# Status_Board.net
KiCad netlist of a schematic drawn in EAGLE
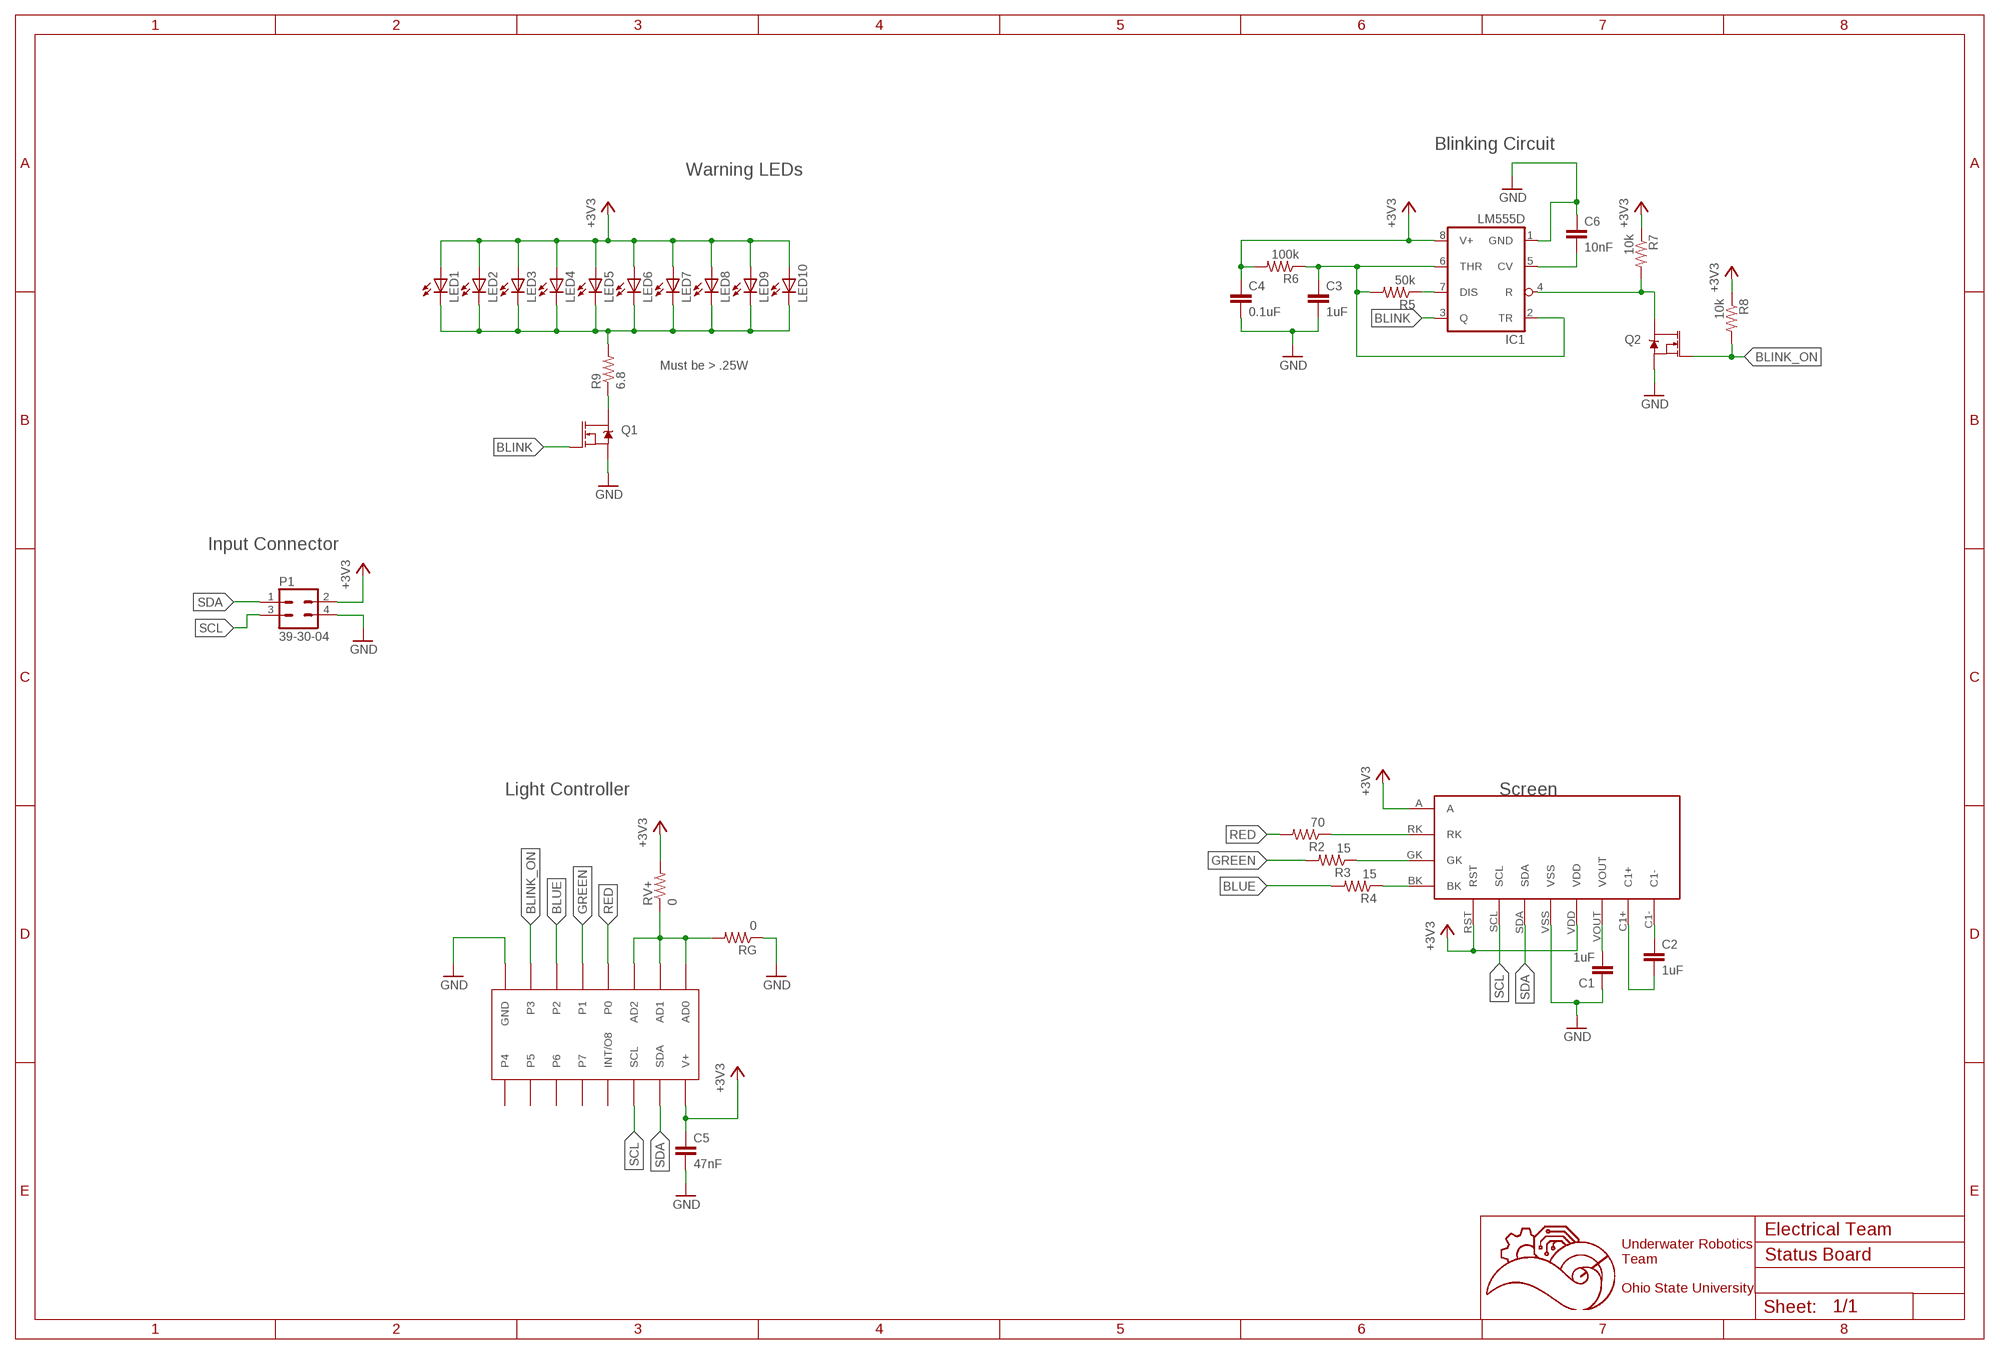
[diagram p0: schematic, sheet 1]

(export (version "E")
  (design (tool "Eeschema 10.0.6"))
  (components
    (comp (ref "C1")
      (value "1uF")
      (footprint "eagle-import:C0603")
      (libsource (lib "eagle-import") (part "C-EUC0603"))
    )
    (comp (ref "C2")
      (value "1uF")
      (footprint "eagle-import:C0603")
      (libsource (lib "eagle-import") (part "C-EUC0603"))
    )
    (comp (ref "C3")
      (value "1uF")
      (footprint "eagle-import:C0603")
      (libsource (lib "eagle-import") (part "C-EUC0603"))
    )
    (comp (ref "C4")
      (value "0.1uF")
      (footprint "eagle-import:C0603")
      (libsource (lib "eagle-import") (part "C-EUC0603"))
    )
    (comp (ref "C5")
      (value "47nF")
      (footprint "eagle-import:C0603")
      (libsource (lib "eagle-import") (part "C-EUC0603"))
    )
    (comp (ref "C6")
      (value "10nF")
      (footprint "eagle-import:C0603")
      (libsource (lib "eagle-import") (part "C-EUC0603"))
    )
    (comp (ref "IC1")
      (value "LM555D")
      (footprint "eagle-import:SO08")
      (libsource (lib "eagle-import") (part "555DLM"))
    )
    (comp (ref "LED1")
      (value "LEDCHIPLED_0603")
      (footprint "eagle-import:CHIPLED_0603")
      (libsource (lib "eagle-import") (part "LEDCHIPLED_0603"))
    )
    (comp (ref "LED2")
      (value "LEDCHIPLED_0603")
      (footprint "eagle-import:CHIPLED_0603")
      (libsource (lib "eagle-import") (part "LEDCHIPLED_0603"))
    )
    (comp (ref "LED3")
      (value "LEDCHIPLED_0603")
      (footprint "eagle-import:CHIPLED_0603")
      (libsource (lib "eagle-import") (part "LEDCHIPLED_0603"))
    )
    (comp (ref "LED4")
      (value "LEDCHIPLED_0603")
      (footprint "eagle-import:CHIPLED_0603")
      (libsource (lib "eagle-import") (part "LEDCHIPLED_0603"))
    )
    (comp (ref "LED5")
      (value "LEDCHIPLED_0603")
      (footprint "eagle-import:CHIPLED_0603")
      (libsource (lib "eagle-import") (part "LEDCHIPLED_0603"))
    )
    (comp (ref "LED6")
      (value "LEDCHIPLED_0603")
      (footprint "eagle-import:CHIPLED_0603")
      (libsource (lib "eagle-import") (part "LEDCHIPLED_0603"))
    )
    (comp (ref "LED7")
      (value "LEDCHIPLED_0603")
      (footprint "eagle-import:CHIPLED_0603")
      (libsource (lib "eagle-import") (part "LEDCHIPLED_0603"))
    )
    (comp (ref "LED8")
      (value "LEDCHIPLED_0603")
      (footprint "eagle-import:CHIPLED_0603")
      (libsource (lib "eagle-import") (part "LEDCHIPLED_0603"))
    )
    (comp (ref "LED9")
      (value "LEDCHIPLED_0603")
      (footprint "eagle-import:CHIPLED_0603")
      (libsource (lib "eagle-import") (part "LEDCHIPLED_0603"))
    )
    (comp (ref "LED10")
      (value "LEDCHIPLED_0603")
      (footprint "eagle-import:CHIPLED_0603")
      (libsource (lib "eagle-import") (part "LEDCHIPLED_0603"))
    )
    (comp (ref "P1")
      (value "39-30-04")
      (footprint "eagle-import:39-30-_04_")
      (libsource (lib "eagle-import") (part "39-30-?04?"))
    )
    (comp (ref "Q1")
      (value "310mA/60V/1.6Ω")
      (footprint "eagle-import:SOT323")
      (libsource (lib "eagle-import") (part "MOSFET-NCH-2N7002PW"))
    )
    (comp (ref "Q2")
      (value "310mA/60V/1.6Ω")
      (footprint "eagle-import:SOT323")
      (libsource (lib "eagle-import") (part "MOSFET-NCH-2N7002PW"))
    )
    (comp (ref "R2")
      (value "70")
      (footprint "eagle-import:R0603")
      (libsource (lib "eagle-import") (part "R-US_R0603"))
    )
    (comp (ref "R3")
      (value "15")
      (footprint "eagle-import:R0603")
      (libsource (lib "eagle-import") (part "R-US_R0603"))
    )
    (comp (ref "R4")
      (value "15")
      (footprint "eagle-import:R0603")
      (libsource (lib "eagle-import") (part "R-US_R0603"))
    )
    (comp (ref "R5")
      (value "50k")
      (footprint "eagle-import:R0603")
      (libsource (lib "eagle-import") (part "R-US_R0603"))
    )
    (comp (ref "R6")
      (value "100k")
      (footprint "eagle-import:R0603")
      (libsource (lib "eagle-import") (part "R-US_R0603"))
    )
    (comp (ref "R7")
      (value "10k")
      (footprint "eagle-import:R0603")
      (libsource (lib "eagle-import") (part "R-US_R0603"))
    )
    (comp (ref "R8")
      (value "10k")
      (footprint "eagle-import:R0603")
      (libsource (lib "eagle-import") (part "R-US_R0603"))
    )
    (comp (ref "R9")
      (value "6.8")
      (footprint "eagle-import:R0603")
      (libsource (lib "eagle-import") (part "R-US_R0603"))
    )
    (comp (ref "RG")
      (value "0")
      (footprint "eagle-import:R0603")
      (libsource (lib "eagle-import") (part "R-US_R0603"))
    )
    (comp (ref "RV+")
      (value "0")
      (footprint "eagle-import:R0603")
      (libsource (lib "eagle-import") (part "R-US_R0603"))
    )
    (comp (ref "U$1")
      (value "NHD-C0220BIZ")
      (footprint "eagle-import:NHD-C0220BIZ")
      (libsource (lib "eagle-import") (part "NHD-C0220BIZ"))
    )
    (comp (ref "U$2")
      (value "MAX7315")
      (footprint "eagle-import:TSSOP-16")
      (libsource (lib "eagle-import") (part "MAX7315"))
    )
  )
  (nets
    (net (code "1") (name "+3V3") (class "Default")
      (node (ref "C4") (pin "1") (pinfunction "1_1") (pintype "passive"))
      (node (ref "C5") (pin "1") (pinfunction "1_1") (pintype "passive"))
      (node (ref "IC1") (pin "8") (pinfunction "V+_8") (pintype "power_in"))
      (node (ref "LED1") (pin "A") (pinfunction "A_A") (pintype "passive"))
      (node (ref "LED10") (pin "A") (pinfunction "A_A") (pintype "passive"))
      (node (ref "LED2") (pin "A") (pinfunction "A_A") (pintype "passive"))
      (node (ref "LED3") (pin "A") (pinfunction "A_A") (pintype "passive"))
      (node (ref "LED4") (pin "A") (pinfunction "A_A") (pintype "passive"))
      (node (ref "LED5") (pin "A") (pinfunction "A_A") (pintype "passive"))
      (node (ref "LED6") (pin "A") (pinfunction "A_A") (pintype "passive"))
      (node (ref "LED7") (pin "A") (pinfunction "A_A") (pintype "passive"))
      (node (ref "LED8") (pin "A") (pinfunction "A_A") (pintype "passive"))
      (node (ref "LED9") (pin "A") (pinfunction "A_A") (pintype "passive"))
      (node (ref "P1") (pin "2") (pinfunction "2_2") (pintype "passive"))
      (node (ref "R6") (pin "2") (pinfunction "2_2") (pintype "passive"))
      (node (ref "R7") (pin "1") (pinfunction "1_1") (pintype "passive"))
      (node (ref "R8") (pin "1") (pinfunction "1_1") (pintype "passive"))
      (node (ref "RV+") (pin "2") (pinfunction "2_2") (pintype "passive"))
      (node (ref "U$1") (pin "A") (pinfunction "A_A") (pintype "bidirectional"))
      (node (ref "U$1") (pin "RST") (pinfunction "RST_RST") (pintype "bidirectional"))
      (node (ref "U$1") (pin "VDD") (pinfunction "VDD_VDD") (pintype "bidirectional"))
      (node (ref "U$2") (pin "16") (pinfunction "V+_16") (pintype "bidirectional"))
    )
    (net (code "2") (name "BLINK") (class "Default")
      (node (ref "IC1") (pin "3") (pinfunction "Q_3") (pintype "output"))
      (node (ref "Q1") (pin "1") (pinfunction "G_1") (pintype "bidirectional"))
    )
    (net (code "3") (name "BLINK_ON") (class "Default")
      (node (ref "Q2") (pin "1") (pinfunction "G_1") (pintype "bidirectional"))
      (node (ref "R8") (pin "2") (pinfunction "2_2") (pintype "passive"))
      (node (ref "U$2") (pin "7") (pinfunction "P3_7") (pintype "bidirectional"))
    )
    (net (code "4") (name "BLUE") (class "Default")
      (node (ref "R4") (pin "2") (pinfunction "2_2") (pintype "passive"))
      (node (ref "U$2") (pin "6") (pinfunction "P2_6") (pintype "bidirectional"))
    )
    (net (code "5") (name "GND") (class "Default")
      (node (ref "C1") (pin "1") (pinfunction "1_1") (pintype "passive"))
      (node (ref "C3") (pin "2") (pinfunction "2_2") (pintype "passive"))
      (node (ref "C4") (pin "2") (pinfunction "2_2") (pintype "passive"))
      (node (ref "C5") (pin "2") (pinfunction "2_2") (pintype "passive"))
      (node (ref "C6") (pin "1") (pinfunction "1_1") (pintype "passive"))
      (node (ref "IC1") (pin "1") (pinfunction "GND_1") (pintype "power_in"))
      (node (ref "P1") (pin "4") (pinfunction "4_4") (pintype "passive"))
      (node (ref "Q1") (pin "2") (pinfunction "S_2") (pintype "bidirectional"))
      (node (ref "Q2") (pin "2") (pinfunction "S_2") (pintype "bidirectional"))
      (node (ref "RG") (pin "1") (pinfunction "1_1") (pintype "passive"))
      (node (ref "U$1") (pin "VSS") (pinfunction "VSS_VSS") (pintype "bidirectional"))
      (node (ref "U$2") (pin "8") (pinfunction "GND_8") (pintype "bidirectional"))
    )
    (net (code "6") (name "GREEN") (class "Default")
      (node (ref "R3") (pin "2") (pinfunction "2_2") (pintype "passive"))
      (node (ref "U$2") (pin "5") (pinfunction "P1_5") (pintype "bidirectional"))
    )
    (net (code "7") (name "Net-(C1-Pad2)") (class "Default")
      (node (ref "C1") (pin "2") (pinfunction "2_2") (pintype "passive"))
      (node (ref "U$1") (pin "VOUT") (pinfunction "VOUT_VOUT") (pintype "bidirectional"))
    )
    (net (code "8") (name "Net-(C2-Pad1)") (class "Default")
      (node (ref "C2") (pin "1") (pinfunction "1_1") (pintype "passive"))
      (node (ref "U$1") (pin "C1-") (pinfunction "C1-_C1-") (pintype "bidirectional"))
    )
    (net (code "9") (name "Net-(C2-Pad2)") (class "Default")
      (node (ref "C2") (pin "2") (pinfunction "2_2") (pintype "passive"))
      (node (ref "U$1") (pin "C1+") (pinfunction "C1+_C1+") (pintype "bidirectional"))
    )
    (net (code "10") (name "Net-(IC1-CV)") (class "Default")
      (node (ref "C6") (pin "2") (pinfunction "2_2") (pintype "passive"))
      (node (ref "IC1") (pin "5") (pinfunction "CV_5") (pintype "input"))
    )
    (net (code "11") (name "Net-(IC1-DIS)") (class "Default")
      (node (ref "IC1") (pin "7") (pinfunction "DIS_7") (pintype "input"))
      (node (ref "R5") (pin "1") (pinfunction "1_1") (pintype "passive"))
    )
    (net (code "12") (name "Net-(IC1-R)") (class "Default")
      (node (ref "IC1") (pin "4") (pinfunction "R_4") (pintype "input"))
      (node (ref "Q2") (pin "3") (pinfunction "D_3") (pintype "bidirectional"))
      (node (ref "R7") (pin "2") (pinfunction "2_2") (pintype "passive"))
    )
    (net (code "13") (name "Net-(IC1-THR)") (class "Default")
      (node (ref "C3") (pin "1") (pinfunction "1_1") (pintype "passive"))
      (node (ref "IC1") (pin "2") (pinfunction "TR_2") (pintype "input"))
      (node (ref "IC1") (pin "6") (pinfunction "THR_6") (pintype "input"))
      (node (ref "R5") (pin "2") (pinfunction "2_2") (pintype "passive"))
      (node (ref "R6") (pin "1") (pinfunction "1_1") (pintype "passive"))
    )
    (net (code "14") (name "Net-(LED1-PadC)") (class "Default")
      (node (ref "LED1") (pin "C") (pinfunction "C_C") (pintype "passive"))
      (node (ref "LED10") (pin "C") (pinfunction "C_C") (pintype "passive"))
      (node (ref "LED2") (pin "C") (pinfunction "C_C") (pintype "passive"))
      (node (ref "LED3") (pin "C") (pinfunction "C_C") (pintype "passive"))
      (node (ref "LED4") (pin "C") (pinfunction "C_C") (pintype "passive"))
      (node (ref "LED5") (pin "C") (pinfunction "C_C") (pintype "passive"))
      (node (ref "LED6") (pin "C") (pinfunction "C_C") (pintype "passive"))
      (node (ref "LED7") (pin "C") (pinfunction "C_C") (pintype "passive"))
      (node (ref "LED8") (pin "C") (pinfunction "C_C") (pintype "passive"))
      (node (ref "LED9") (pin "C") (pinfunction "C_C") (pintype "passive"))
      (node (ref "R9") (pin "2") (pinfunction "2_2") (pintype "passive"))
    )
    (net (code "15") (name "Net-(Q1-D)") (class "Default")
      (node (ref "Q1") (pin "3") (pinfunction "D_3") (pintype "bidirectional"))
      (node (ref "R9") (pin "1") (pinfunction "1_1") (pintype "passive"))
    )
    (net (code "16") (name "Net-(R2-Pad1)") (class "Default")
      (node (ref "R2") (pin "1") (pinfunction "1_1") (pintype "passive"))
      (node (ref "U$1") (pin "RK") (pinfunction "RK_RK") (pintype "bidirectional"))
    )
    (net (code "17") (name "Net-(R3-Pad1)") (class "Default")
      (node (ref "R3") (pin "1") (pinfunction "1_1") (pintype "passive"))
      (node (ref "U$1") (pin "GK") (pinfunction "GK_GK") (pintype "bidirectional"))
    )
    (net (code "18") (name "Net-(R4-Pad1)") (class "Default")
      (node (ref "R4") (pin "1") (pinfunction "1_1") (pintype "passive"))
      (node (ref "U$1") (pin "BK") (pinfunction "BK_BK") (pintype "bidirectional"))
    )
    (net (code "19") (name "Net-(U$2-AD0)") (class "Default")
      (node (ref "RG") (pin "2") (pinfunction "2_2") (pintype "passive"))
      (node (ref "RV+") (pin "1") (pinfunction "1_1") (pintype "passive"))
      (node (ref "U$2") (pin "1") (pinfunction "AD0_1") (pintype "bidirectional"))
      (node (ref "U$2") (pin "2") (pinfunction "AD1_2") (pintype "bidirectional"))
      (node (ref "U$2") (pin "3") (pinfunction "AD2_3") (pintype "bidirectional"))
    )
    (net (code "20") (name "RED") (class "Default")
      (node (ref "R2") (pin "2") (pinfunction "2_2") (pintype "passive"))
      (node (ref "U$2") (pin "4") (pinfunction "P0_4") (pintype "bidirectional"))
    )
    (net (code "21") (name "SCL") (class "Default")
      (node (ref "P1") (pin "3") (pinfunction "3_3") (pintype "passive"))
      (node (ref "U$1") (pin "SCL") (pinfunction "SCL_SCL") (pintype "bidirectional"))
      (node (ref "U$2") (pin "14") (pinfunction "SCL_14") (pintype "bidirectional"))
    )
    (net (code "22") (name "SDA") (class "Default")
      (node (ref "P1") (pin "1") (pinfunction "1_1") (pintype "passive"))
      (node (ref "U$1") (pin "SDA") (pinfunction "SDA_SDA") (pintype "bidirectional"))
      (node (ref "U$2") (pin "15") (pinfunction "SDA_15") (pintype "bidirectional"))
    )
    (net (code "23") (name "unconnected-(U$2-INT{slash}O8-Pad13)") (class "Default")
      (node (ref "U$2") (pin "13") (pinfunction "INT/O8_13") (pintype "bidirectional"))
    )
    (net (code "24") (name "unconnected-(U$2-P4-Pad9)") (class "Default")
      (node (ref "U$2") (pin "9") (pinfunction "P4_9") (pintype "bidirectional"))
    )
    (net (code "25") (name "unconnected-(U$2-P5-Pad10)") (class "Default")
      (node (ref "U$2") (pin "10") (pinfunction "P5_10") (pintype "bidirectional"))
    )
    (net (code "26") (name "unconnected-(U$2-P6-Pad11)") (class "Default")
      (node (ref "U$2") (pin "11") (pinfunction "P6_11") (pintype "bidirectional"))
    )
    (net (code "27") (name "unconnected-(U$2-P7-Pad12)") (class "Default")
      (node (ref "U$2") (pin "12") (pinfunction "P7_12") (pintype "bidirectional"))
    )
  )
)
